# XLR_BAL_OUT_2026-02-06.net
KiCad netlist of a schematic drawn in EasyEDA Pro
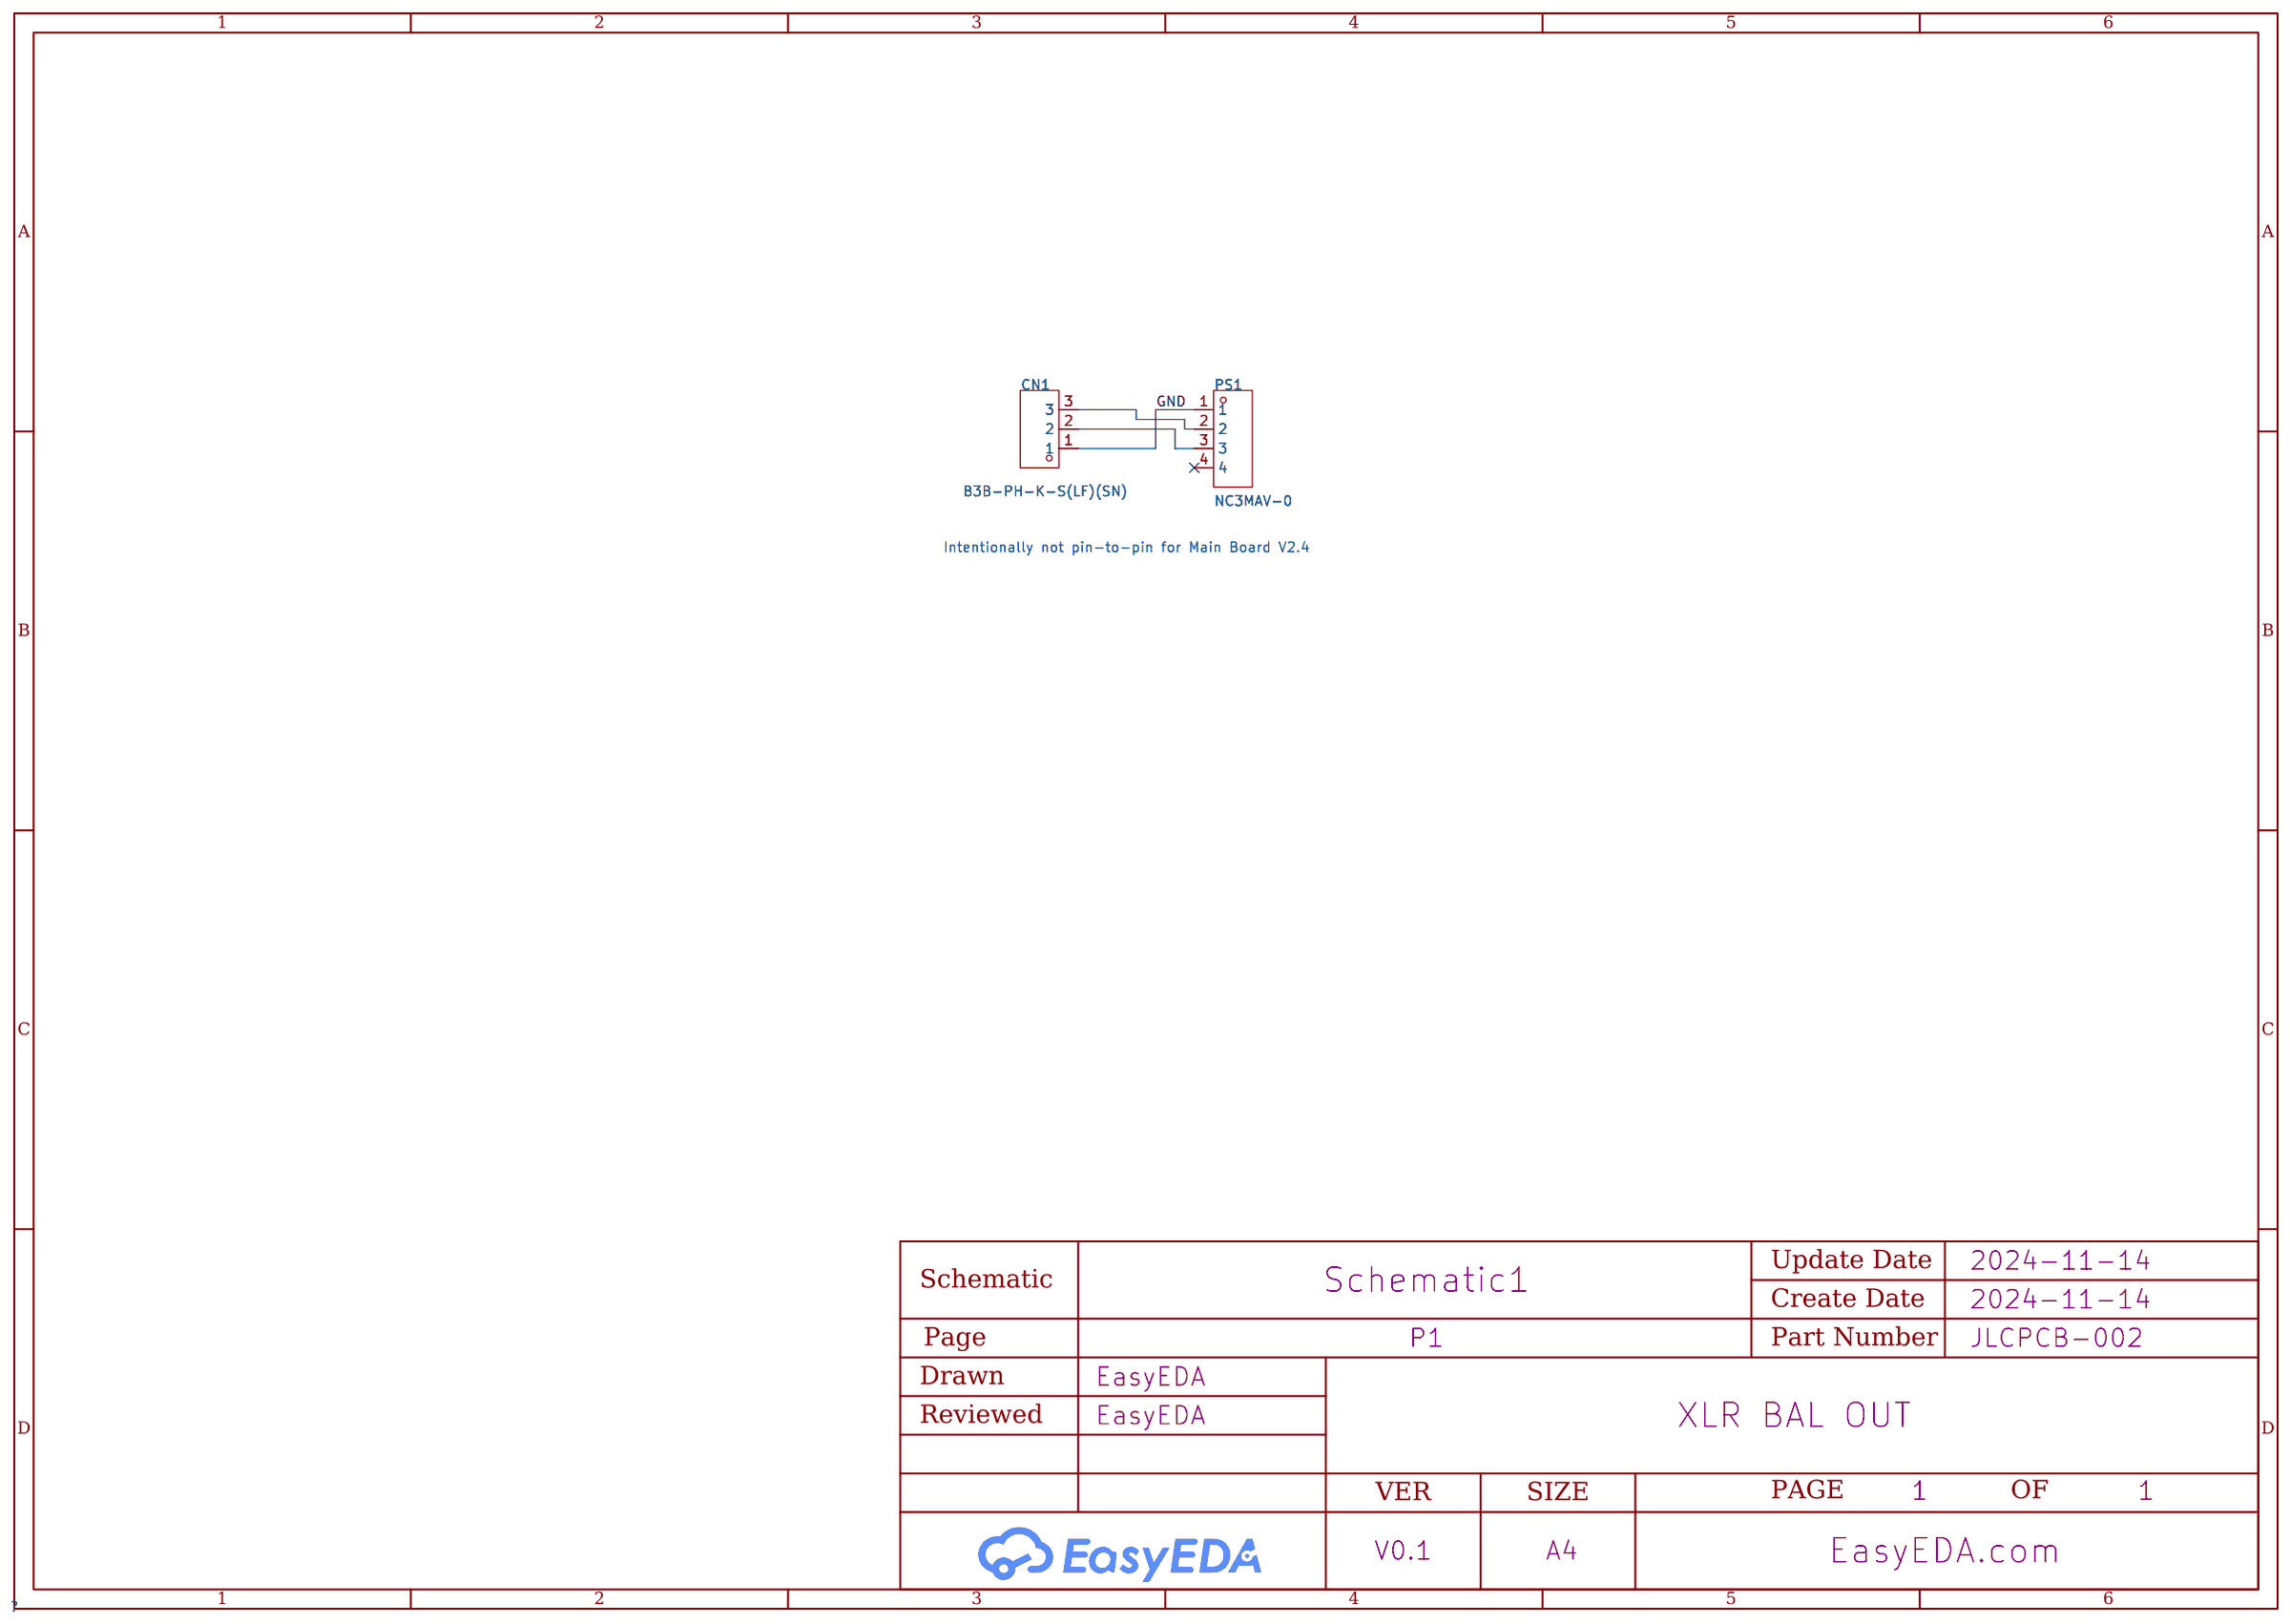
[diagram p0: schematic sheet]

(export (version "E")
  (design (tool "Eeschema 10.0.6"))
  (components
    (comp (ref "CN1")
      (value "B3B-PH-K-S(LF)(SN)")
      (footprint "easyedapro:CONN-TH_B3B-PH-K-S")
      (fields (field (name "Manufacturer") "JST"))
      (libsource (lib "easyedapro") (part "B3B-PH-K-S(LF)(SN)"))
    )
    (comp (ref "PS1")
      (value "NC3MAV-0")
      (footprint "easyedapro:CONN-TH_NC3MAV-0")
      (fields (field (name "Manufacturer") "NEUTRIK(优曲克)"))
      (libsource (lib "easyedapro") (part "NC3MAV-0"))
    )
  )
  (nets
    (net (code "1") (name "/GND") (class "Default")
      (node (ref "CN1") (pin "1") (pinfunction "1_1") (pintype "unspecified"))
      (node (ref "PS1") (pin "1") (pinfunction "1_1") (pintype "unspecified"))
    )
    (net (code "2") (name "Net-(CN1-Pad2)") (class "Default")
      (node (ref "CN1") (pin "2") (pinfunction "2_2") (pintype "unspecified"))
      (node (ref "PS1") (pin "3") (pinfunction "3_3") (pintype "unspecified"))
    )
    (net (code "3") (name "Net-(CN1-Pad3)") (class "Default")
      (node (ref "CN1") (pin "3") (pinfunction "3_3") (pintype "unspecified"))
      (node (ref "PS1") (pin "2") (pinfunction "2_2") (pintype "unspecified"))
    )
    (net (code "4") (name "unconnected-(PS1-Pad4)") (class "Default")
      (node (ref "PS1") (pin "4") (pinfunction "4_4") (pintype "unspecified+no_connect"))
    )
  )
)
